# SLaB.net
KiCad netlist of a schematic drawn in EAGLE
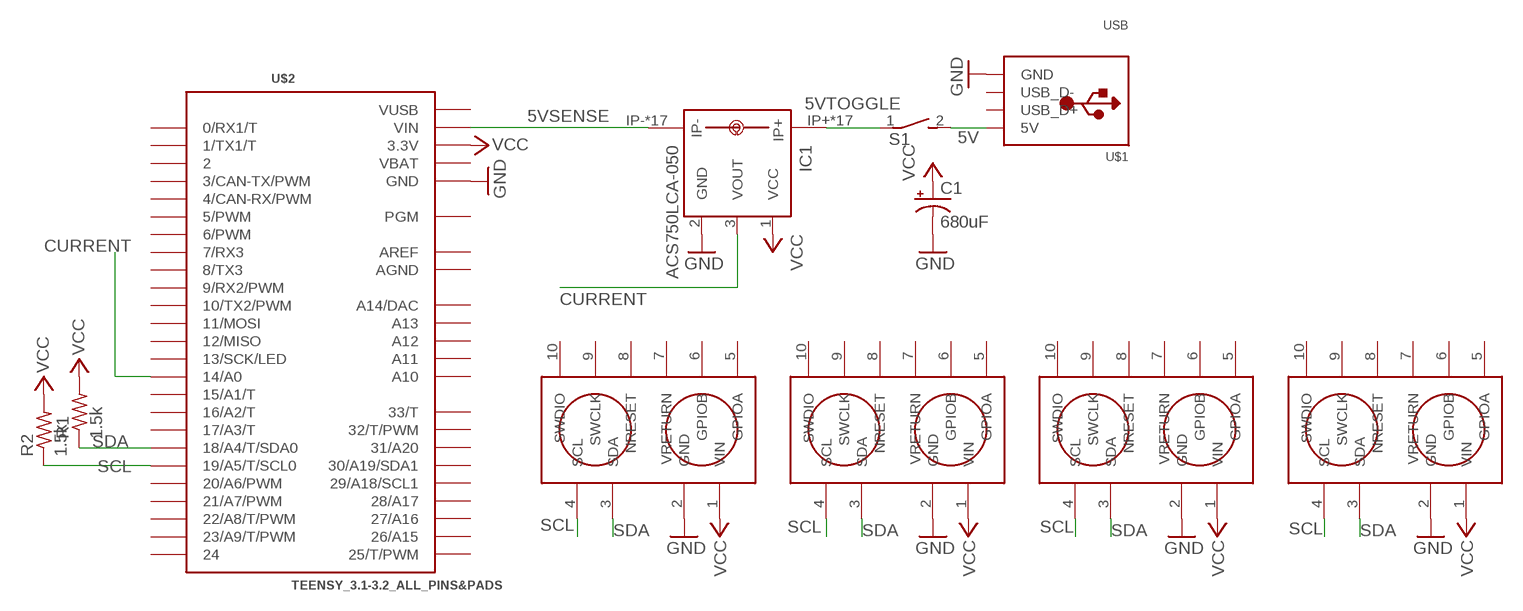
[diagram p0: schematic, sheet 1]

(export (version "E")
  (design (tool "Eeschema 10.0.6"))
  (components
    (comp (ref "C1")
      (value "680uF")
      (footprint "eagle-import:E2-5")
      (libsource (lib "eagle-import") (part "CPOL-USE2-5"))
    )
    (comp (ref "IC1")
      (value "ACS750LCA-050")
      (footprint "eagle-import:ACS75050")
      (fields (field (name "MF") "ALLEGRO MICROSYSTEMS, INC."))
      (libsource (lib "eagle-import") (part "ACS750CA-050L"))
    )
    (comp (ref "R1")
      (value "1.5k")
      (footprint "eagle-import:0204_7")
      (libsource (lib "eagle-import") (part "R-US_0204/7"))
    )
    (comp (ref "R2")
      (value "1.5k")
      (footprint "eagle-import:0204_7")
      (libsource (lib "eagle-import") (part "R-US_0204/7"))
    )
    (comp (ref "S1")
      (value "DS01E")
      (footprint "eagle-import:DS-01")
      (libsource (lib "eagle-import") (part "DS01E"))
    )
    (comp (ref "U$1")
      (value "USB")
      (footprint "eagle-import:USB")
      (libsource (lib "eagle-import") (part "USB"))
    )
    (comp (ref "U$2")
      (value "TEENSY_3.1-3.2_ALL_PINS&PADS")
      (footprint "eagle-import:TEENSY_3.0-3.2_ALL_PINS_&_PADS")
      (libsource (lib "eagle-import") (part "TEENSY_3.1-3.2_ALL_PINS&PADS"))
    )
    (comp (ref "U$3")
      (value "LIDAR")
      (footprint "eagle-import:LIDAR")
      (libsource (lib "eagle-import") (part "LIDAR"))
    )
    (comp (ref "U$4")
      (value "LIDAR")
      (footprint "eagle-import:LIDAR")
      (libsource (lib "eagle-import") (part "LIDAR"))
    )
    (comp (ref "U$5")
      (value "LIDAR")
      (footprint "eagle-import:LIDAR")
      (libsource (lib "eagle-import") (part "LIDAR"))
    )
    (comp (ref "U$6")
      (value "LIDAR")
      (footprint "eagle-import:LIDAR")
      (libsource (lib "eagle-import") (part "LIDAR"))
    )
  )
  (nets
    (net (code "1") (name "/5V") (class "Default")
      (node (ref "S1") (pin "2") (pinfunction "2_2") (pintype "passive"))
      (node (ref "U$1") (pin "5V") (pinfunction "5V_5V") (pintype "power_in"))
    )
    (net (code "2") (name "/5VSENSE") (class "Default")
      (node (ref "IC1") (pin "IP-") (pinfunction "IP-_IP-") (pintype "passive"))
      (node (ref "IC1") (pin "IP-@10") (pinfunction "IP-_IP-@10") (pintype "passive"))
      (node (ref "IC1") (pin "IP-@11") (pinfunction "IP-_IP-@11") (pintype "passive"))
      (node (ref "IC1") (pin "IP-@12") (pinfunction "IP-_IP-@12") (pintype "passive"))
      (node (ref "IC1") (pin "IP-@13") (pinfunction "IP-_IP-@13") (pintype "passive"))
      (node (ref "IC1") (pin "IP-@14") (pinfunction "IP-_IP-@14") (pintype "passive"))
      (node (ref "IC1") (pin "IP-@15") (pinfunction "IP-_IP-@15") (pintype "passive"))
      (node (ref "IC1") (pin "IP-@16") (pinfunction "IP-_IP-@16") (pintype "passive"))
      (node (ref "IC1") (pin "IP-@17") (pinfunction "IP-_IP-@17") (pintype "passive"))
      (node (ref "IC1") (pin "IP-@2") (pinfunction "IP-_IP-@2") (pintype "passive"))
      (node (ref "IC1") (pin "IP-@3") (pinfunction "IP-_IP-@3") (pintype "passive"))
      (node (ref "IC1") (pin "IP-@4") (pinfunction "IP-_IP-@4") (pintype "passive"))
      (node (ref "IC1") (pin "IP-@5") (pinfunction "IP-_IP-@5") (pintype "passive"))
      (node (ref "IC1") (pin "IP-@6") (pinfunction "IP-_IP-@6") (pintype "passive"))
      (node (ref "IC1") (pin "IP-@7") (pinfunction "IP-_IP-@7") (pintype "passive"))
      (node (ref "IC1") (pin "IP-@8") (pinfunction "IP-_IP-@8") (pintype "passive"))
      (node (ref "IC1") (pin "IP-@9") (pinfunction "IP-_IP-@9") (pintype "passive"))
      (node (ref "U$2") (pin "VIN") (pinfunction "VIN_VIN") (pintype "power_in"))
    )
    (net (code "3") (name "/5VTOGGLE") (class "Default")
      (node (ref "IC1") (pin "IP+") (pinfunction "IP+_IP+") (pintype "passive"))
      (node (ref "IC1") (pin "IP+@10") (pinfunction "IP+_IP+@10") (pintype "passive"))
      (node (ref "IC1") (pin "IP+@11") (pinfunction "IP+_IP+@11") (pintype "passive"))
      (node (ref "IC1") (pin "IP+@12") (pinfunction "IP+_IP+@12") (pintype "passive"))
      (node (ref "IC1") (pin "IP+@13") (pinfunction "IP+_IP+@13") (pintype "passive"))
      (node (ref "IC1") (pin "IP+@14") (pinfunction "IP+_IP+@14") (pintype "passive"))
      (node (ref "IC1") (pin "IP+@15") (pinfunction "IP+_IP+@15") (pintype "passive"))
      (node (ref "IC1") (pin "IP+@16") (pinfunction "IP+_IP+@16") (pintype "passive"))
      (node (ref "IC1") (pin "IP+@17") (pinfunction "IP+_IP+@17") (pintype "passive"))
      (node (ref "IC1") (pin "IP+@2") (pinfunction "IP+_IP+@2") (pintype "passive"))
      (node (ref "IC1") (pin "IP+@3") (pinfunction "IP+_IP+@3") (pintype "passive"))
      (node (ref "IC1") (pin "IP+@4") (pinfunction "IP+_IP+@4") (pintype "passive"))
      (node (ref "IC1") (pin "IP+@5") (pinfunction "IP+_IP+@5") (pintype "passive"))
      (node (ref "IC1") (pin "IP+@6") (pinfunction "IP+_IP+@6") (pintype "passive"))
      (node (ref "IC1") (pin "IP+@7") (pinfunction "IP+_IP+@7") (pintype "passive"))
      (node (ref "IC1") (pin "IP+@8") (pinfunction "IP+_IP+@8") (pintype "passive"))
      (node (ref "IC1") (pin "IP+@9") (pinfunction "IP+_IP+@9") (pintype "passive"))
      (node (ref "S1") (pin "1") (pinfunction "1_1") (pintype "passive"))
    )
    (net (code "4") (name "/AGND") (class "Default")
      (node (ref "U$2") (pin "AGND") (pinfunction "AGND_AGND") (pintype "power_in"))
    )
    (net (code "5") (name "/AREF") (class "Default")
      (node (ref "U$2") (pin "AREF") (pinfunction "AREF_AREF") (pintype "power_in"))
    )
    (net (code "6") (name "/CURRENT") (class "Default")
      (node (ref "IC1") (pin "3") (pinfunction "VOUT_3") (pintype "output"))
      (node (ref "U$2") (pin "14/A0") (pinfunction "14/A0_14/A0") (pintype "bidirectional"))
    )
    (net (code "7") (name "/SCL") (class "Default")
      (node (ref "R2") (pin "1") (pinfunction "1_1") (pintype "passive"))
      (node (ref "U$2") (pin "19/A5") (pinfunction "19/A5/T/SCL0_19/A5") (pintype "bidirectional"))
      (node (ref "U$3") (pin "4") (pinfunction "SCL_4") (pintype "bidirectional"))
      (node (ref "U$4") (pin "4") (pinfunction "SCL_4") (pintype "bidirectional"))
      (node (ref "U$5") (pin "4") (pinfunction "SCL_4") (pintype "bidirectional"))
      (node (ref "U$6") (pin "4") (pinfunction "SCL_4") (pintype "bidirectional"))
    )
    (net (code "8") (name "/SDA") (class "Default")
      (node (ref "R1") (pin "1") (pinfunction "1_1") (pintype "passive"))
      (node (ref "U$2") (pin "18/A4") (pinfunction "18/A4/T/SDA0_18/A4") (pintype "bidirectional"))
      (node (ref "U$3") (pin "3") (pinfunction "SDA_3") (pintype "bidirectional"))
      (node (ref "U$4") (pin "3") (pinfunction "SDA_3") (pintype "bidirectional"))
      (node (ref "U$5") (pin "3") (pinfunction "SDA_3") (pintype "bidirectional"))
      (node (ref "U$6") (pin "3") (pinfunction "SDA_3") (pintype "bidirectional"))
    )
    (net (code "9") (name "/VBAT") (class "Default")
      (node (ref "U$2") (pin "VBAT") (pinfunction "VBAT_VBAT") (pintype "power_in"))
    )
    (net (code "10") (name "/VUSB") (class "Default")
      (node (ref "U$2") (pin "VUSB") (pinfunction "VUSB_VUSB") (pintype "power_in"))
    )
    (net (code "11") (name "GND") (class "Default")
      (node (ref "C1") (pin "-") (pinfunction "-_-") (pintype "passive"))
      (node (ref "IC1") (pin "2") (pinfunction "GND_2") (pintype "power_in"))
      (node (ref "U$1") (pin "GND") (pinfunction "GND_GND") (pintype "power_in"))
      (node (ref "U$2") (pin "GND") (pinfunction "GND_GND") (pintype "power_in"))
      (node (ref "U$2") (pin "GND1") (pinfunction "GND_GND1") (pintype "power_in"))
      (node (ref "U$2") (pin "GND2") (pinfunction "GND_GND2") (pintype "power_in"))
      (node (ref "U$3") (pin "2") (pinfunction "GND_2") (pintype "bidirectional"))
      (node (ref "U$4") (pin "2") (pinfunction "GND_2") (pintype "bidirectional"))
      (node (ref "U$5") (pin "2") (pinfunction "GND_2") (pintype "bidirectional"))
      (node (ref "U$6") (pin "2") (pinfunction "GND_2") (pintype "bidirectional"))
    )
    (net (code "12") (name "VCC") (class "Default")
      (node (ref "C1") (pin "+") (pinfunction "+_+") (pintype "passive"))
      (node (ref "IC1") (pin "1") (pinfunction "VCC_1") (pintype "power_in"))
      (node (ref "R1") (pin "2") (pinfunction "2_2") (pintype "passive"))
      (node (ref "R2") (pin "2") (pinfunction "2_2") (pintype "passive"))
      (node (ref "U$2") (pin "3.3V") (pinfunction "3.3V_3.3V") (pintype "power_in"))
      (node (ref "U$2") (pin "3.3V1") (pinfunction "3.3V_3.3V1") (pintype "power_in"))
      (node (ref "U$2") (pin "3.3V2") (pinfunction "3.3V_3.3V2") (pintype "power_in"))
      (node (ref "U$3") (pin "1") (pinfunction "VIN_1") (pintype "bidirectional"))
      (node (ref "U$4") (pin "1") (pinfunction "VIN_1") (pintype "bidirectional"))
      (node (ref "U$5") (pin "1") (pinfunction "VIN_1") (pintype "bidirectional"))
      (node (ref "U$6") (pin "1") (pinfunction "VIN_1") (pintype "bidirectional"))
    )
    (net (code "13") (name "unconnected-(U$1-PadUSB_D+)") (class "Default")
      (node (ref "U$1") (pin "USB_D+") (pinfunction "USB_D+_USB_D+") (pintype "bidirectional"))
    )
    (net (code "14") (name "unconnected-(U$1-PadUSB_D-)") (class "Default")
      (node (ref "U$1") (pin "USB_D-") (pinfunction "USB_D-_USB_D-") (pintype "bidirectional"))
    )
    (net (code "15") (name "unconnected-(U$2-0{slash}RX1{slash}T-Pad0)") (class "Default")
      (node (ref "U$2") (pin "0") (pinfunction "0/RX1/T_0") (pintype "bidirectional"))
    )
    (net (code "16") (name "unconnected-(U$2-1{slash}TX1{slash}T-Pad1)") (class "Default")
      (node (ref "U$2") (pin "1") (pinfunction "1/TX1/T_1") (pintype "bidirectional"))
    )
    (net (code "17") (name "unconnected-(U$2-3{slash}CAN-TX{slash}PWM-Pad3)") (class "Default")
      (node (ref "U$2") (pin "3") (pinfunction "3/CAN-TX/PWM_3") (pintype "bidirectional"))
    )
    (net (code "18") (name "unconnected-(U$2-4{slash}CAN-RX{slash}PWM-Pad4)") (class "Default")
      (node (ref "U$2") (pin "4") (pinfunction "4/CAN-RX/PWM_4") (pintype "bidirectional"))
    )
    (net (code "19") (name "unconnected-(U$2-5{slash}PWM-Pad5)") (class "Default")
      (node (ref "U$2") (pin "5") (pinfunction "5/PWM_5") (pintype "bidirectional"))
    )
    (net (code "20") (name "unconnected-(U$2-6{slash}PWM-Pad6)") (class "Default")
      (node (ref "U$2") (pin "6") (pinfunction "6/PWM_6") (pintype "bidirectional"))
    )
    (net (code "21") (name "unconnected-(U$2-7{slash}RX3-Pad7)") (class "Default")
      (node (ref "U$2") (pin "7") (pinfunction "7/RX3_7") (pintype "bidirectional"))
    )
    (net (code "22") (name "unconnected-(U$2-8{slash}TX3-Pad8)") (class "Default")
      (node (ref "U$2") (pin "8") (pinfunction "8/TX3_8") (pintype "bidirectional"))
    )
    (net (code "23") (name "unconnected-(U$2-9{slash}RX2{slash}PWM-Pad9)") (class "Default")
      (node (ref "U$2") (pin "9") (pinfunction "9/RX2/PWM_9") (pintype "bidirectional"))
    )
    (net (code "24") (name "unconnected-(U$2-10{slash}TX2{slash}PWM-Pad10)") (class "Default")
      (node (ref "U$2") (pin "10") (pinfunction "10/TX2/PWM_10") (pintype "bidirectional"))
    )
    (net (code "25") (name "unconnected-(U$2-11{slash}MOSI-Pad11)") (class "Default")
      (node (ref "U$2") (pin "11") (pinfunction "11/MOSI_11") (pintype "bidirectional"))
    )
    (net (code "26") (name "unconnected-(U$2-12{slash}MISO-Pad12)") (class "Default")
      (node (ref "U$2") (pin "12") (pinfunction "12/MISO_12") (pintype "bidirectional"))
    )
    (net (code "27") (name "unconnected-(U$2-13{slash}SCK{slash}LED-Pad13)") (class "Default")
      (node (ref "U$2") (pin "13") (pinfunction "13/SCK/LED_13") (pintype "bidirectional"))
    )
    (net (code "28") (name "unconnected-(U$2-15{slash}A1{slash}T-Pad15{slash}A1)") (class "Default")
      (node (ref "U$2") (pin "15/A1") (pinfunction "15/A1/T_15/A1") (pintype "bidirectional"))
    )
    (net (code "29") (name "unconnected-(U$2-16{slash}A2{slash}T-Pad16{slash}A2)") (class "Default")
      (node (ref "U$2") (pin "16/A2") (pinfunction "16/A2/T_16/A2") (pintype "bidirectional"))
    )
    (net (code "30") (name "unconnected-(U$2-17{slash}A3{slash}T-Pad17{slash}A3)") (class "Default")
      (node (ref "U$2") (pin "17/A3") (pinfunction "17/A3/T_17/A3") (pintype "bidirectional"))
    )
    (net (code "31") (name "unconnected-(U$2-20{slash}A6{slash}PWM-Pad20{slash}A6)") (class "Default")
      (node (ref "U$2") (pin "20/A6") (pinfunction "20/A6/PWM_20/A6") (pintype "bidirectional"))
    )
    (net (code "32") (name "unconnected-(U$2-21{slash}A7{slash}PWM-Pad21{slash}A7)") (class "Default")
      (node (ref "U$2") (pin "21/A7") (pinfunction "21/A7/PWM_21/A7") (pintype "bidirectional"))
    )
    (net (code "33") (name "unconnected-(U$2-22{slash}A8{slash}T{slash}PWM-Pad22{slash}A8)") (class "Default")
      (node (ref "U$2") (pin "22/A8") (pinfunction "22/A8/T/PWM_22/A8") (pintype "bidirectional"))
    )
    (net (code "34") (name "unconnected-(U$2-23{slash}A9{slash}T{slash}PWM-Pad23{slash}A9)") (class "Default")
      (node (ref "U$2") (pin "23/A9") (pinfunction "23/A9/T/PWM_23/A9") (pintype "bidirectional"))
    )
    (net (code "35") (name "unconnected-(U$2-25{slash}T{slash}PWM-Pad25)") (class "Default")
      (node (ref "U$2") (pin "25") (pinfunction "25/T/PWM_25") (pintype "bidirectional"))
    )
    (net (code "36") (name "unconnected-(U$2-26{slash}A15-Pad26)") (class "Default")
      (node (ref "U$2") (pin "26") (pinfunction "26/A15_26") (pintype "bidirectional"))
    )
    (net (code "37") (name "unconnected-(U$2-27{slash}A16-Pad27)") (class "Default")
      (node (ref "U$2") (pin "27") (pinfunction "27/A16_27") (pintype "bidirectional"))
    )
    (net (code "38") (name "unconnected-(U$2-28{slash}A17-Pad28)") (class "Default")
      (node (ref "U$2") (pin "28") (pinfunction "28/A17_28") (pintype "bidirectional"))
    )
    (net (code "39") (name "unconnected-(U$2-29{slash}A18{slash}SCL1-Pad29)") (class "Default")
      (node (ref "U$2") (pin "29") (pinfunction "29/A18/SCL1_29") (pintype "bidirectional"))
    )
    (net (code "40") (name "unconnected-(U$2-30{slash}A19{slash}SDA1-Pad30)") (class "Default")
      (node (ref "U$2") (pin "30") (pinfunction "30/A19/SDA1_30") (pintype "bidirectional"))
    )
    (net (code "41") (name "unconnected-(U$2-31{slash}A20-Pad31)") (class "Default")
      (node (ref "U$2") (pin "31") (pinfunction "31/A20_31") (pintype "bidirectional"))
    )
    (net (code "42") (name "unconnected-(U$2-32{slash}T{slash}PWM-Pad32)") (class "Default")
      (node (ref "U$2") (pin "32") (pinfunction "32/T/PWM_32") (pintype "bidirectional"))
    )
    (net (code "43") (name "unconnected-(U$2-33{slash}T-Pad33)") (class "Default")
      (node (ref "U$2") (pin "33") (pinfunction "33/T_33") (pintype "bidirectional"))
    )
    (net (code "44") (name "unconnected-(U$2-A14{slash}DAC-PadRESET{slash}DAC)") (class "Default")
      (node (ref "U$2") (pin "RESET/DAC") (pinfunction "A14/DAC_RESET/DAC") (pintype "bidirectional"))
    )
    (net (code "45") (name "unconnected-(U$2-Pad2)") (class "Default")
      (node (ref "U$2") (pin "2") (pinfunction "2_2") (pintype "bidirectional"))
    )
    (net (code "46") (name "unconnected-(U$2-Pad24)") (class "Default")
      (node (ref "U$2") (pin "24") (pinfunction "24_24") (pintype "bidirectional"))
    )
    (net (code "47") (name "unconnected-(U$2-PadA10)") (class "Default")
      (node (ref "U$2") (pin "A10") (pinfunction "A10_A10") (pintype "bidirectional"))
    )
    (net (code "48") (name "unconnected-(U$2-PadA11)") (class "Default")
      (node (ref "U$2") (pin "A11") (pinfunction "A11_A11") (pintype "bidirectional"))
    )
    (net (code "49") (name "unconnected-(U$2-PadA12)") (class "Default")
      (node (ref "U$2") (pin "A12") (pinfunction "A12_A12") (pintype "bidirectional"))
    )
    (net (code "50") (name "unconnected-(U$2-PadA13)") (class "Default")
      (node (ref "U$2") (pin "A13") (pinfunction "A13_A13") (pintype "bidirectional"))
    )
    (net (code "51") (name "unconnected-(U$2-PadPGM)") (class "Default")
      (node (ref "U$2") (pin "PGM") (pinfunction "PGM_PGM") (pintype "bidirectional"))
    )
    (net (code "52") (name "unconnected-(U$3-GPIOA-Pad5)") (class "Default")
      (node (ref "U$3") (pin "5") (pinfunction "GPIOA_5") (pintype "bidirectional"))
    )
    (net (code "53") (name "unconnected-(U$3-GPIOB-Pad6)") (class "Default")
      (node (ref "U$3") (pin "6") (pinfunction "GPIOB_6") (pintype "bidirectional"))
    )
    (net (code "54") (name "unconnected-(U$3-NRESET-Pad8)") (class "Default")
      (node (ref "U$3") (pin "8") (pinfunction "NRESET_8") (pintype "bidirectional"))
    )
    (net (code "55") (name "unconnected-(U$3-SWCLK-Pad9)") (class "Default")
      (node (ref "U$3") (pin "9") (pinfunction "SWCLK_9") (pintype "bidirectional"))
    )
    (net (code "56") (name "unconnected-(U$3-SWDIO-Pad10)") (class "Default")
      (node (ref "U$3") (pin "10") (pinfunction "SWDIO_10") (pintype "bidirectional"))
    )
    (net (code "57") (name "unconnected-(U$3-VRETURN-Pad7)") (class "Default")
      (node (ref "U$3") (pin "7") (pinfunction "VRETURN_7") (pintype "bidirectional"))
    )
    (net (code "58") (name "unconnected-(U$4-GPIOA-Pad5)") (class "Default")
      (node (ref "U$4") (pin "5") (pinfunction "GPIOA_5") (pintype "bidirectional"))
    )
    (net (code "59") (name "unconnected-(U$4-GPIOB-Pad6)") (class "Default")
      (node (ref "U$4") (pin "6") (pinfunction "GPIOB_6") (pintype "bidirectional"))
    )
    (net (code "60") (name "unconnected-(U$4-NRESET-Pad8)") (class "Default")
      (node (ref "U$4") (pin "8") (pinfunction "NRESET_8") (pintype "bidirectional"))
    )
    (net (code "61") (name "unconnected-(U$4-SWCLK-Pad9)") (class "Default")
      (node (ref "U$4") (pin "9") (pinfunction "SWCLK_9") (pintype "bidirectional"))
    )
    (net (code "62") (name "unconnected-(U$4-SWDIO-Pad10)") (class "Default")
      (node (ref "U$4") (pin "10") (pinfunction "SWDIO_10") (pintype "bidirectional"))
    )
    (net (code "63") (name "unconnected-(U$4-VRETURN-Pad7)") (class "Default")
      (node (ref "U$4") (pin "7") (pinfunction "VRETURN_7") (pintype "bidirectional"))
    )
    (net (code "64") (name "unconnected-(U$5-GPIOA-Pad5)") (class "Default")
      (node (ref "U$5") (pin "5") (pinfunction "GPIOA_5") (pintype "bidirectional"))
    )
    (net (code "65") (name "unconnected-(U$5-GPIOB-Pad6)") (class "Default")
      (node (ref "U$5") (pin "6") (pinfunction "GPIOB_6") (pintype "bidirectional"))
    )
    (net (code "66") (name "unconnected-(U$5-NRESET-Pad8)") (class "Default")
      (node (ref "U$5") (pin "8") (pinfunction "NRESET_8") (pintype "bidirectional"))
    )
    (net (code "67") (name "unconnected-(U$5-SWCLK-Pad9)") (class "Default")
      (node (ref "U$5") (pin "9") (pinfunction "SWCLK_9") (pintype "bidirectional"))
    )
    (net (code "68") (name "unconnected-(U$5-SWDIO-Pad10)") (class "Default")
      (node (ref "U$5") (pin "10") (pinfunction "SWDIO_10") (pintype "bidirectional"))
    )
    (net (code "69") (name "unconnected-(U$5-VRETURN-Pad7)") (class "Default")
      (node (ref "U$5") (pin "7") (pinfunction "VRETURN_7") (pintype "bidirectional"))
    )
    (net (code "70") (name "unconnected-(U$6-GPIOA-Pad5)") (class "Default")
      (node (ref "U$6") (pin "5") (pinfunction "GPIOA_5") (pintype "bidirectional"))
    )
    (net (code "71") (name "unconnected-(U$6-GPIOB-Pad6)") (class "Default")
      (node (ref "U$6") (pin "6") (pinfunction "GPIOB_6") (pintype "bidirectional"))
    )
    (net (code "72") (name "unconnected-(U$6-NRESET-Pad8)") (class "Default")
      (node (ref "U$6") (pin "8") (pinfunction "NRESET_8") (pintype "bidirectional"))
    )
    (net (code "73") (name "unconnected-(U$6-SWCLK-Pad9)") (class "Default")
      (node (ref "U$6") (pin "9") (pinfunction "SWCLK_9") (pintype "bidirectional"))
    )
    (net (code "74") (name "unconnected-(U$6-SWDIO-Pad10)") (class "Default")
      (node (ref "U$6") (pin "10") (pinfunction "SWDIO_10") (pintype "bidirectional"))
    )
    (net (code "75") (name "unconnected-(U$6-VRETURN-Pad7)") (class "Default")
      (node (ref "U$6") (pin "7") (pinfunction "VRETURN_7") (pintype "bidirectional"))
    )
  )
)
